# USB2517.net
KiCad netlist of a schematic drawn in Altium Designer
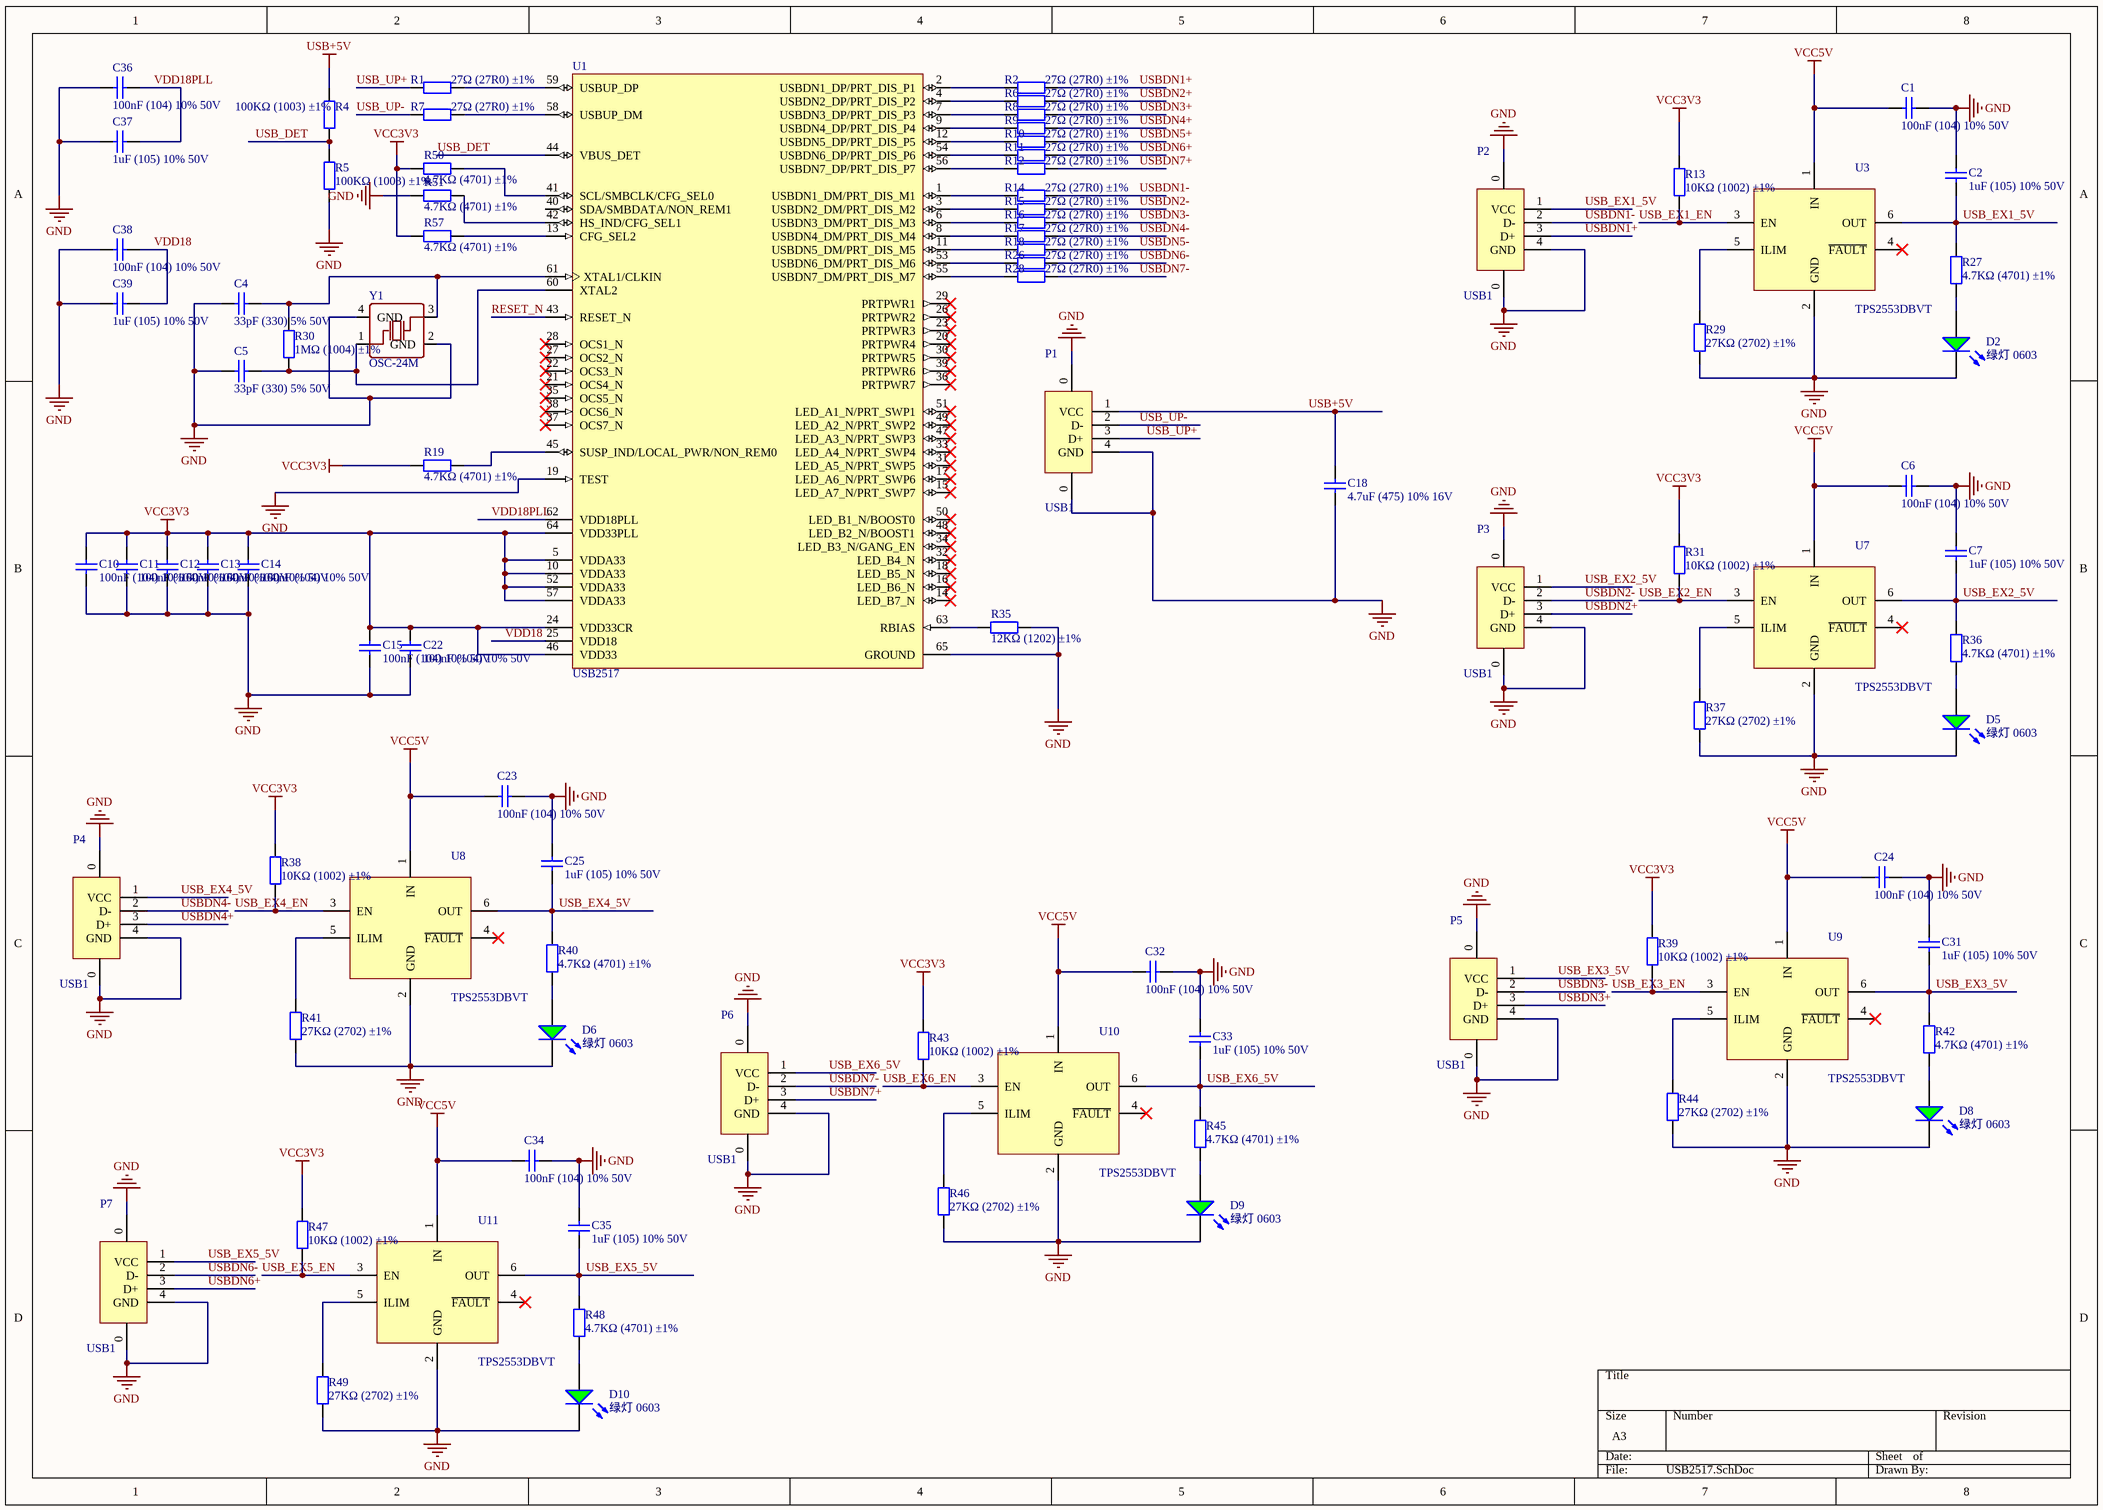
[diagram p0: USB2517.SchDoc]

(export (version "E")
  (design (tool "Eeschema 10.0.6"))
  (components
    (comp (ref "C1")
      (value "100nF (104) 10% 50V")
      (footprint "0603_C")
      (description "贴片电容")
      (libsource (lib "AD封装2018.9.19Miscellaneous Devices LC") (part "0603 100nF (104) 10% 50V"))
    )
    (comp (ref "C2")
      (value "1uF (105) 10% 50V")
      (footprint "0603_C")
      (description "贴片电容")
      (libsource (lib "AD封装2018.9.19Miscellaneous Devices LC") (part "0603 1uF (105) 10% 50V"))
    )
    (comp (ref "C4")
      (value "33pF (330) 5% 50V")
      (footprint "0603_C")
      (description "贴片电容")
      (libsource (lib "AD封装2018.9.19Miscellaneous Devices LC") (part "0603 33pF (330) 5% 50V"))
    )
    (comp (ref "C5")
      (value "33pF (330) 5% 50V")
      (footprint "0603_C")
      (description "贴片电容")
      (libsource (lib "AD封装2018.9.19Miscellaneous Devices LC") (part "0603 33pF (330) 5% 50V"))
    )
    (comp (ref "C6")
      (value "100nF (104) 10% 50V")
      (footprint "0603_C")
      (description "贴片电容")
      (libsource (lib "AD封装2018.9.19Miscellaneous Devices LC") (part "0603 100nF (104) 10% 50V"))
    )
    (comp (ref "C7")
      (value "1uF (105) 10% 50V")
      (footprint "0603_C")
      (description "贴片电容")
      (libsource (lib "AD封装2018.9.19Miscellaneous Devices LC") (part "0603 1uF (105) 10% 50V"))
    )
    (comp (ref "C10")
      (value "100nF (104) 10% 50V")
      (footprint "0603_C")
      (description "贴片电容")
      (libsource (lib "AD封装2018.9.19Miscellaneous Devices LC") (part "0603 100nF (104) 10% 50V"))
    )
    (comp (ref "C11")
      (value "100nF (104) 10% 50V")
      (footprint "0603_C")
      (description "贴片电容")
      (libsource (lib "AD封装2018.9.19Miscellaneous Devices LC") (part "0603 100nF (104) 10% 50V"))
    )
    (comp (ref "C12")
      (value "100nF (104) 10% 50V")
      (footprint "0603_C")
      (description "贴片电容")
      (libsource (lib "AD封装2018.9.19Miscellaneous Devices LC") (part "0603 100nF (104) 10% 50V"))
    )
    (comp (ref "C13")
      (value "100nF (104) 10% 50V")
      (footprint "0603_C")
      (description "贴片电容")
      (libsource (lib "AD封装2018.9.19Miscellaneous Devices LC") (part "0603 100nF (104) 10% 50V"))
    )
    (comp (ref "C14")
      (value "100nF (104) 10% 50V")
      (footprint "0603_C")
      (description "贴片电容")
      (libsource (lib "AD封装2018.9.19Miscellaneous Devices LC") (part "0603 100nF (104) 10% 50V"))
    )
    (comp (ref "C15")
      (value "100nF (104) 10% 50V")
      (footprint "0603_C")
      (description "贴片电容")
      (libsource (lib "AD封装2018.9.19Miscellaneous Devices LC") (part "0603 100nF (104) 10% 50V"))
    )
    (comp (ref "C18")
      (value "4.7uF (475) 10% 16V")
      (footprint "0603_C")
      (description "贴片电容")
      (libsource (lib "AD封装2018.9.19Miscellaneous Devices LC") (part "0603 4.7uF (475) 10% 16V"))
    )
    (comp (ref "C22")
      (value "100nF (104) 10% 50V")
      (footprint "0603_C")
      (description "贴片电容")
      (libsource (lib "AD封装2018.9.19Miscellaneous Devices LC") (part "0603 100nF (104) 10% 50V"))
    )
    (comp (ref "C23")
      (value "100nF (104) 10% 50V")
      (footprint "0603_C")
      (description "贴片电容")
      (libsource (lib "AD封装2018.9.19Miscellaneous Devices LC") (part "0603 100nF (104) 10% 50V"))
    )
    (comp (ref "C24")
      (value "100nF (104) 10% 50V")
      (footprint "0603_C")
      (description "贴片电容")
      (libsource (lib "AD封装2018.9.19Miscellaneous Devices LC") (part "0603 100nF (104) 10% 50V"))
    )
    (comp (ref "C25")
      (value "1uF (105) 10% 50V")
      (footprint "0603_C")
      (description "贴片电容")
      (libsource (lib "AD封装2018.9.19Miscellaneous Devices LC") (part "0603 1uF (105) 10% 50V"))
    )
    (comp (ref "C31")
      (value "1uF (105) 10% 50V")
      (footprint "0603_C")
      (description "贴片电容")
      (libsource (lib "AD封装2018.9.19Miscellaneous Devices LC") (part "0603 1uF (105) 10% 50V"))
    )
    (comp (ref "C32")
      (value "100nF (104) 10% 50V")
      (footprint "0603_C")
      (description "贴片电容")
      (libsource (lib "AD封装2018.9.19Miscellaneous Devices LC") (part "0603 100nF (104) 10% 50V"))
    )
    (comp (ref "C33")
      (value "1uF (105) 10% 50V")
      (footprint "0603_C")
      (description "贴片电容")
      (libsource (lib "AD封装2018.9.19Miscellaneous Devices LC") (part "0603 1uF (105) 10% 50V"))
    )
    (comp (ref "C34")
      (value "100nF (104) 10% 50V")
      (footprint "0603_C")
      (description "贴片电容")
      (libsource (lib "AD封装2018.9.19Miscellaneous Devices LC") (part "0603 100nF (104) 10% 50V"))
    )
    (comp (ref "C35")
      (value "1uF (105) 10% 50V")
      (footprint "0603_C")
      (description "贴片电容")
      (libsource (lib "AD封装2018.9.19Miscellaneous Devices LC") (part "0603 1uF (105) 10% 50V"))
    )
    (comp (ref "C36")
      (value "100nF (104) 10% 50V")
      (footprint "0603_C")
      (description "贴片电容")
      (libsource (lib "AD封装2018.9.19Miscellaneous Devices LC") (part "0603 100nF (104) 10% 50V"))
    )
    (comp (ref "C37")
      (value "1uF (105) 10% 50V")
      (footprint "0603_C")
      (description "贴片电容")
      (libsource (lib "AD封装2018.9.19Miscellaneous Devices LC") (part "0603 1uF (105) 10% 50V"))
    )
    (comp (ref "C38")
      (value "100nF (104) 10% 50V")
      (footprint "0603_C")
      (description "贴片电容")
      (libsource (lib "AD封装2018.9.19Miscellaneous Devices LC") (part "0603 100nF (104) 10% 50V"))
    )
    (comp (ref "C39")
      (value "1uF (105) 10% 50V")
      (footprint "0603_C")
      (description "贴片电容")
      (libsource (lib "AD封装2018.9.19Miscellaneous Devices LC") (part "0603 1uF (105) 10% 50V"))
    )
    (comp (ref "D2")
      (value "绿灯 0603")
      (footprint "0603_LED_S1")
      (description "发光二极管")
      (libsource (lib "AD封装2018.9.19Miscellaneous Devices LC") (part "0603 绿灯"))
    )
    (comp (ref "D5")
      (value "绿灯 0603")
      (footprint "0603_LED_S1")
      (description "发光二极管")
      (libsource (lib "AD封装2018.9.19Miscellaneous Devices LC") (part "0603 绿灯"))
    )
    (comp (ref "D6")
      (value "绿灯 0603")
      (footprint "0603_LED_S1")
      (description "发光二极管")
      (libsource (lib "AD封装2018.9.19Miscellaneous Devices LC") (part "0603 绿灯"))
    )
    (comp (ref "D8")
      (value "绿灯 0603")
      (footprint "0603_LED_S1")
      (description "发光二极管")
      (libsource (lib "AD封装2018.9.19Miscellaneous Devices LC") (part "0603 绿灯"))
    )
    (comp (ref "D9")
      (value "绿灯 0603")
      (footprint "0603_LED_S1")
      (description "发光二极管")
      (libsource (lib "AD封装2018.9.19Miscellaneous Devices LC") (part "0603 绿灯"))
    )
    (comp (ref "D10")
      (value "绿灯 0603")
      (footprint "0603_LED_S1")
      (description "发光二极管")
      (libsource (lib "AD封装2018.9.19Miscellaneous Devices LC") (part "0603 绿灯"))
    )
    (comp (ref "P1") (value "USB1") (footprint "USB-B-TH_USB-B01") (libsource (lib "我的集成库") (part "USB1")))
    (comp (ref "P2")
      (value "USB1")
      (footprint "USB-A-TH_AF90-OFFSET - duplicate")
      (libsource (lib "我的集成库") (part "USB1"))
    )
    (comp (ref "P3")
      (value "USB1")
      (footprint "USB-A-TH_AF90-OFFSET - duplicate")
      (libsource (lib "我的集成库") (part "USB1"))
    )
    (comp (ref "P4")
      (value "USB1")
      (footprint "USB-A-TH_AF90-OFFSET - duplicate")
      (libsource (lib "我的集成库") (part "USB1"))
    )
    (comp (ref "P5")
      (value "USB1")
      (footprint "USB-A-TH_AF90-OFFSET - duplicate")
      (libsource (lib "我的集成库") (part "USB1"))
    )
    (comp (ref "P6")
      (value "USB1")
      (footprint "USB-A-TH_AF90-OFFSET - duplicate")
      (libsource (lib "我的集成库") (part "USB1"))
    )
    (comp (ref "P7")
      (value "USB1")
      (footprint "USB-A-TH_AF90-OFFSET - duplicate")
      (libsource (lib "我的集成库") (part "USB1"))
    )
    (comp (ref "R1")
      (value "27Ω (27R0) ±1%")
      (footprint "0603_R")
      (description "贴片电阻")
      (libsource (lib "AD封装2018.9.19Miscellaneous Devices LC") (part "0603 27Ω (27R0) 1%"))
    )
    (comp (ref "R2")
      (value "27Ω (27R0) ±1%")
      (footprint "0603_R")
      (description "贴片电阻")
      (libsource (lib "AD封装2018.9.19Miscellaneous Devices LC") (part "0603 27Ω (27R0) 1%"))
    )
    (comp (ref "R4")
      (value "100KΩ (1003) ±1%")
      (footprint "0603_R")
      (description "贴片电阻")
      (libsource (lib "AD封装2018.9.19Miscellaneous Devices LC") (part "0603 100KΩ (1003) 1%"))
    )
    (comp (ref "R5")
      (value "100KΩ (1003) ±1%")
      (footprint "0603_R")
      (description "贴片电阻")
      (libsource (lib "AD封装2018.9.19Miscellaneous Devices LC") (part "0603 100KΩ (1003) 1%"))
    )
    (comp (ref "R6")
      (value "27Ω (27R0) ±1%")
      (footprint "0603_R")
      (description "贴片电阻")
      (libsource (lib "AD封装2018.9.19Miscellaneous Devices LC") (part "0603 27Ω (27R0) 1%"))
    )
    (comp (ref "R7")
      (value "27Ω (27R0) ±1%")
      (footprint "0603_R")
      (description "贴片电阻")
      (libsource (lib "AD封装2018.9.19Miscellaneous Devices LC") (part "0603 27Ω (27R0) 1%"))
    )
    (comp (ref "R8")
      (value "27Ω (27R0) ±1%")
      (footprint "0603_R")
      (description "贴片电阻")
      (libsource (lib "AD封装2018.9.19Miscellaneous Devices LC") (part "0603 27Ω (27R0) 1%"))
    )
    (comp (ref "R9")
      (value "27Ω (27R0) ±1%")
      (footprint "0603_R")
      (description "贴片电阻")
      (libsource (lib "AD封装2018.9.19Miscellaneous Devices LC") (part "0603 27Ω (27R0) 1%"))
    )
    (comp (ref "R10")
      (value "27Ω (27R0) ±1%")
      (footprint "0603_R")
      (description "贴片电阻")
      (libsource (lib "AD封装2018.9.19Miscellaneous Devices LC") (part "0603 27Ω (27R0) 1%"))
    )
    (comp (ref "R11")
      (value "27Ω (27R0) ±1%")
      (footprint "0603_R")
      (description "贴片电阻")
      (libsource (lib "AD封装2018.9.19Miscellaneous Devices LC") (part "0603 27Ω (27R0) 1%"))
    )
    (comp (ref "R12")
      (value "27Ω (27R0) ±1%")
      (footprint "0603_R")
      (description "贴片电阻")
      (libsource (lib "AD封装2018.9.19Miscellaneous Devices LC") (part "0603 27Ω (27R0) 1%"))
    )
    (comp (ref "R13")
      (value "10KΩ (1002) ±1%")
      (footprint "0603_R")
      (description "贴片电阻")
      (libsource (lib "AD封装2018.9.19Miscellaneous Devices LC") (part "0603 10KΩ (1002) 1%"))
    )
    (comp (ref "R14")
      (value "27Ω (27R0) ±1%")
      (footprint "0603_R")
      (description "贴片电阻")
      (libsource (lib "AD封装2018.9.19Miscellaneous Devices LC") (part "0603 27Ω (27R0) 1%"))
    )
    (comp (ref "R15")
      (value "27Ω (27R0) ±1%")
      (footprint "0603_R")
      (description "贴片电阻")
      (libsource (lib "AD封装2018.9.19Miscellaneous Devices LC") (part "0603 27Ω (27R0) 1%"))
    )
    (comp (ref "R16")
      (value "27Ω (27R0) ±1%")
      (footprint "0603_R")
      (description "贴片电阻")
      (libsource (lib "AD封装2018.9.19Miscellaneous Devices LC") (part "0603 27Ω (27R0) 1%"))
    )
    (comp (ref "R17")
      (value "27Ω (27R0) ±1%")
      (footprint "0603_R")
      (description "贴片电阻")
      (libsource (lib "AD封装2018.9.19Miscellaneous Devices LC") (part "0603 27Ω (27R0) 1%"))
    )
    (comp (ref "R18")
      (value "27Ω (27R0) ±1%")
      (footprint "0603_R")
      (description "贴片电阻")
      (libsource (lib "AD封装2018.9.19Miscellaneous Devices LC") (part "0603 27Ω (27R0) 1%"))
    )
    (comp (ref "R19")
      (value "4.7KΩ (4701) ±1%")
      (footprint "0603_R")
      (description "贴片电阻")
      (libsource (lib "") (part "0603 4.7KΩ (4701) 1%_2"))
    )
    (comp (ref "R26")
      (value "27Ω (27R0) ±1%")
      (footprint "0603_R")
      (description "贴片电阻")
      (libsource (lib "AD封装2018.9.19Miscellaneous Devices LC") (part "0603 27Ω (27R0) 1%"))
    )
    (comp (ref "R27")
      (value "4.7KΩ (4701) ±1%")
      (footprint "0603_R")
      (description "贴片电阻")
      (libsource (lib "AD封装2018.9.19Miscellaneous Devices LC") (part "0603 4.7KΩ (4701) 1%"))
    )
    (comp (ref "R28")
      (value "27Ω (27R0) ±1%")
      (footprint "0603_R")
      (description "贴片电阻")
      (libsource (lib "AD封装2018.9.19Miscellaneous Devices LC") (part "0603 27Ω (27R0) 1%"))
    )
    (comp (ref "R29")
      (value "27KΩ (2702) ±1%")
      (footprint "0603_R")
      (description "贴片电阻")
      (libsource (lib "AD封装2018.9.19Miscellaneous Devices LC") (part "0603 27KΩ (2702) 1%"))
    )
    (comp (ref "R30")
      (value "1MΩ (1004) ±1%")
      (footprint "0603_R")
      (description "贴片电阻")
      (libsource (lib "AD封装2018.9.19Miscellaneous Devices LC") (part "0603 1MΩ (1004) 1%"))
    )
    (comp (ref "R31")
      (value "10KΩ (1002) ±1%")
      (footprint "0603_R")
      (description "贴片电阻")
      (libsource (lib "AD封装2018.9.19Miscellaneous Devices LC") (part "0603 10KΩ (1002) 1%"))
    )
    (comp (ref "R35")
      (value "12KΩ (1202) ±1%")
      (footprint "0603_R")
      (description "贴片电阻")
      (libsource (lib "AD封装2018.9.19Miscellaneous Devices LC") (part "0603 12KΩ (1202) 1%"))
    )
    (comp (ref "R36")
      (value "4.7KΩ (4701) ±1%")
      (footprint "0603_R")
      (description "贴片电阻")
      (libsource (lib "AD封装2018.9.19Miscellaneous Devices LC") (part "0603 4.7KΩ (4701) 1%"))
    )
    (comp (ref "R37")
      (value "27KΩ (2702) ±1%")
      (footprint "0603_R")
      (description "贴片电阻")
      (libsource (lib "AD封装2018.9.19Miscellaneous Devices LC") (part "0603 27KΩ (2702) 1%"))
    )
    (comp (ref "R38")
      (value "10KΩ (1002) ±1%")
      (footprint "0603_R")
      (description "贴片电阻")
      (libsource (lib "AD封装2018.9.19Miscellaneous Devices LC") (part "0603 10KΩ (1002) 1%"))
    )
    (comp (ref "R39")
      (value "10KΩ (1002) ±1%")
      (footprint "0603_R")
      (description "贴片电阻")
      (libsource (lib "AD封装2018.9.19Miscellaneous Devices LC") (part "0603 10KΩ (1002) 1%"))
    )
    (comp (ref "R40")
      (value "4.7KΩ (4701) ±1%")
      (footprint "0603_R")
      (description "贴片电阻")
      (libsource (lib "AD封装2018.9.19Miscellaneous Devices LC") (part "0603 4.7KΩ (4701) 1%"))
    )
    (comp (ref "R41")
      (value "27KΩ (2702) ±1%")
      (footprint "0603_R")
      (description "贴片电阻")
      (libsource (lib "AD封装2018.9.19Miscellaneous Devices LC") (part "0603 27KΩ (2702) 1%"))
    )
    (comp (ref "R42")
      (value "4.7KΩ (4701) ±1%")
      (footprint "0603_R")
      (description "贴片电阻")
      (libsource (lib "AD封装2018.9.19Miscellaneous Devices LC") (part "0603 4.7KΩ (4701) 1%"))
    )
    (comp (ref "R43")
      (value "10KΩ (1002) ±1%")
      (footprint "0603_R")
      (description "贴片电阻")
      (libsource (lib "AD封装2018.9.19Miscellaneous Devices LC") (part "0603 10KΩ (1002) 1%"))
    )
    (comp (ref "R44")
      (value "27KΩ (2702) ±1%")
      (footprint "0603_R")
      (description "贴片电阻")
      (libsource (lib "AD封装2018.9.19Miscellaneous Devices LC") (part "0603 27KΩ (2702) 1%"))
    )
    (comp (ref "R45")
      (value "4.7KΩ (4701) ±1%")
      (footprint "0603_R")
      (description "贴片电阻")
      (libsource (lib "AD封装2018.9.19Miscellaneous Devices LC") (part "0603 4.7KΩ (4701) 1%"))
    )
    (comp (ref "R46")
      (value "27KΩ (2702) ±1%")
      (footprint "0603_R")
      (description "贴片电阻")
      (libsource (lib "AD封装2018.9.19Miscellaneous Devices LC") (part "0603 27KΩ (2702) 1%"))
    )
    (comp (ref "R47")
      (value "10KΩ (1002) ±1%")
      (footprint "0603_R")
      (description "贴片电阻")
      (libsource (lib "AD封装2018.9.19Miscellaneous Devices LC") (part "0603 10KΩ (1002) 1%"))
    )
    (comp (ref "R48")
      (value "4.7KΩ (4701) ±1%")
      (footprint "0603_R")
      (description "贴片电阻")
      (libsource (lib "AD封装2018.9.19Miscellaneous Devices LC") (part "0603 4.7KΩ (4701) 1%"))
    )
    (comp (ref "R49")
      (value "27KΩ (2702) ±1%")
      (footprint "0603_R")
      (description "贴片电阻")
      (libsource (lib "AD封装2018.9.19Miscellaneous Devices LC") (part "0603 27KΩ (2702) 1%"))
    )
    (comp (ref "R50")
      (value "4.7KΩ (4701) ±1%")
      (footprint "0603_R")
      (description "贴片电阻")
      (libsource (lib "") (part "0603 4.7KΩ (4701) 1%_1"))
    )
    (comp (ref "R51")
      (value "4.7KΩ (4701) ±1%")
      (footprint "0603_R")
      (description "贴片电阻")
      (libsource (lib "") (part "0603 4.7KΩ (4701) 1%_1"))
    )
    (comp (ref "R57")
      (value "4.7KΩ (4701) ±1%")
      (footprint "0603_R")
      (description "贴片电阻")
      (libsource (lib "") (part "0603 4.7KΩ (4701) 1%_1"))
    )
    (comp (ref "U1") (value "USB2517") (footprint "QFN-64") (libsource (lib "我的集成库") (part "USB2517-JZX")))
    (comp (ref "U3")
      (value "TPS2553DBVT")
      (footprint "SOT-23-6")
      (description "SOT-23-6")
      (libsource (lib "我的集成库") (part "TPS2553DBVT"))
    )
    (comp (ref "U7")
      (value "TPS2553DBVT")
      (footprint "SOT-23-6")
      (description "SOT-23-6")
      (libsource (lib "我的集成库") (part "TPS2553DBVT"))
    )
    (comp (ref "U8")
      (value "TPS2553DBVT")
      (footprint "SOT-23-6")
      (description "SOT-23-6")
      (libsource (lib "我的集成库") (part "TPS2553DBVT"))
    )
    (comp (ref "U9")
      (value "TPS2553DBVT")
      (footprint "SOT-23-6")
      (description "SOT-23-6")
      (libsource (lib "我的集成库") (part "TPS2553DBVT"))
    )
    (comp (ref "U10")
      (value "TPS2553DBVT")
      (footprint "SOT-23-6")
      (description "SOT-23-6")
      (libsource (lib "我的集成库") (part "TPS2553DBVT"))
    )
    (comp (ref "U11")
      (value "TPS2553DBVT")
      (footprint "SOT-23-6")
      (description "SOT-23-6")
      (libsource (lib "我的集成库") (part "TPS2553DBVT"))
    )
    (comp (ref "Y1")
      (value "OSC-24M")
      (footprint "SMD-3225_4P")
      (description "SMD-3225_4P")
      (libsource (lib "我的集成库") (part "OSC-24M"))
    )
  )
  (nets
    (net (code "1") (name "/RESET_N") (class "Default")
      (node (ref "U1") (pin "43") (pinfunction "RESET_N_43") (pintype "input"))
    )
    (net (code "2") (name "/USBDN1+") (class "Default")
      (node (ref "P2") (pin "3") (pinfunction "D+_3") (pintype "passive"))
      (node (ref "R2") (pin "2") (pinfunction "2_2") (pintype "passive"))
    )
    (net (code "3") (name "/USBDN1-") (class "Default")
      (node (ref "P2") (pin "2") (pinfunction "D-_2") (pintype "passive"))
      (node (ref "R14") (pin "2") (pinfunction "2_2") (pintype "passive"))
    )
    (net (code "4") (name "/USBDN2+") (class "Default")
      (node (ref "P3") (pin "3") (pinfunction "D+_3") (pintype "passive"))
      (node (ref "R6") (pin "2") (pinfunction "2_2") (pintype "passive"))
    )
    (net (code "5") (name "/USBDN2-") (class "Default")
      (node (ref "P3") (pin "2") (pinfunction "D-_2") (pintype "passive"))
      (node (ref "R15") (pin "2") (pinfunction "2_2") (pintype "passive"))
    )
    (net (code "6") (name "/USBDN3+") (class "Default")
      (node (ref "P5") (pin "3") (pinfunction "D+_3") (pintype "passive"))
      (node (ref "R8") (pin "2") (pinfunction "2_2") (pintype "passive"))
    )
    (net (code "7") (name "/USBDN3-") (class "Default")
      (node (ref "P5") (pin "2") (pinfunction "D-_2") (pintype "passive"))
      (node (ref "R16") (pin "2") (pinfunction "2_2") (pintype "passive"))
    )
    (net (code "8") (name "/USBDN4+") (class "Default")
      (node (ref "P4") (pin "3") (pinfunction "D+_3") (pintype "passive"))
      (node (ref "R9") (pin "2") (pinfunction "2_2") (pintype "passive"))
    )
    (net (code "9") (name "/USBDN4-") (class "Default")
      (node (ref "P4") (pin "2") (pinfunction "D-_2") (pintype "passive"))
      (node (ref "R17") (pin "2") (pinfunction "2_2") (pintype "passive"))
    )
    (net (code "10") (name "/USBDN5+") (class "Default")
      (node (ref "R10") (pin "2") (pinfunction "2_2") (pintype "passive"))
    )
    (net (code "11") (name "/USBDN5-") (class "Default")
      (node (ref "R18") (pin "2") (pinfunction "2_2") (pintype "passive"))
    )
    (net (code "12") (name "/USBDN6+") (class "Default")
      (node (ref "P7") (pin "3") (pinfunction "D+_3") (pintype "passive"))
      (node (ref "R11") (pin "2") (pinfunction "2_2") (pintype "passive"))
    )
    (net (code "13") (name "/USBDN6-") (class "Default")
      (node (ref "P7") (pin "2") (pinfunction "D-_2") (pintype "passive"))
      (node (ref "R26") (pin "2") (pinfunction "2_2") (pintype "passive"))
    )
    (net (code "14") (name "/USBDN7+") (class "Default")
      (node (ref "P6") (pin "3") (pinfunction "D+_3") (pintype "passive"))
      (node (ref "R12") (pin "2") (pinfunction "2_2") (pintype "passive"))
    )
    (net (code "15") (name "/USBDN7-") (class "Default")
      (node (ref "P6") (pin "2") (pinfunction "D-_2") (pintype "passive"))
      (node (ref "R28") (pin "2") (pinfunction "2_2") (pintype "passive"))
    )
    (net (code "16") (name "/USB_DET") (class "Default")
      (node (ref "R4") (pin "1") (pinfunction "1_1") (pintype "passive"))
      (node (ref "R5") (pin "2") (pinfunction "2_2") (pintype "passive"))
      (node (ref "U1") (pin "44") (pinfunction "VBUS_DET_44") (pintype "bidirectional"))
    )
    (net (code "17") (name "/USB_EX1_5V") (class "Default")
      (node (ref "C2") (pin "1") (pinfunction "1_1") (pintype "passive"))
      (node (ref "P2") (pin "1") (pinfunction "VCC_1") (pintype "passive"))
      (node (ref "R27") (pin "2") (pinfunction "2_2") (pintype "passive"))
      (node (ref "U3") (pin "6") (pinfunction "OUT_6") (pintype "passive"))
    )
    (net (code "18") (name "/USB_EX1_EN") (class "Default")
      (node (ref "R13") (pin "1") (pinfunction "1_1") (pintype "passive"))
      (node (ref "U3") (pin "3") (pinfunction "EN_3") (pintype "passive"))
    )
    (net (code "19") (name "/USB_EX2_5V") (class "Default")
      (node (ref "C7") (pin "1") (pinfunction "1_1") (pintype "passive"))
      (node (ref "P3") (pin "1") (pinfunction "VCC_1") (pintype "passive"))
      (node (ref "R36") (pin "2") (pinfunction "2_2") (pintype "passive"))
      (node (ref "U7") (pin "6") (pinfunction "OUT_6") (pintype "passive"))
    )
    (net (code "20") (name "/USB_EX2_EN") (class "Default")
      (node (ref "R31") (pin "1") (pinfunction "1_1") (pintype "passive"))
      (node (ref "U7") (pin "3") (pinfunction "EN_3") (pintype "passive"))
    )
    (net (code "21") (name "/USB_EX3_5V") (class "Default")
      (node (ref "C31") (pin "1") (pinfunction "1_1") (pintype "passive"))
      (node (ref "P5") (pin "1") (pinfunction "VCC_1") (pintype "passive"))
      (node (ref "R42") (pin "2") (pinfunction "2_2") (pintype "passive"))
      (node (ref "U9") (pin "6") (pinfunction "OUT_6") (pintype "passive"))
    )
    (net (code "22") (name "/USB_EX3_EN") (class "Default")
      (node (ref "R39") (pin "1") (pinfunction "1_1") (pintype "passive"))
      (node (ref "U9") (pin "3") (pinfunction "EN_3") (pintype "passive"))
    )
    (net (code "23") (name "/USB_EX4_5V") (class "Default")
      (node (ref "C25") (pin "1") (pinfunction "1_1") (pintype "passive"))
      (node (ref "P4") (pin "1") (pinfunction "VCC_1") (pintype "passive"))
      (node (ref "R40") (pin "2") (pinfunction "2_2") (pintype "passive"))
      (node (ref "U8") (pin "6") (pinfunction "OUT_6") (pintype "passive"))
    )
    (net (code "24") (name "/USB_EX4_EN") (class "Default")
      (node (ref "R38") (pin "1") (pinfunction "1_1") (pintype "passive"))
      (node (ref "U8") (pin "3") (pinfunction "EN_3") (pintype "passive"))
    )
    (net (code "25") (name "/USB_EX5_5V") (class "Default")
      (node (ref "C35") (pin "1") (pinfunction "1_1") (pintype "passive"))
      (node (ref "P7") (pin "1") (pinfunction "VCC_1") (pintype "passive"))
      (node (ref "R48") (pin "2") (pinfunction "2_2") (pintype "passive"))
      (node (ref "U11") (pin "6") (pinfunction "OUT_6") (pintype "passive"))
    )
    (net (code "26") (name "/USB_EX5_EN") (class "Default")
      (node (ref "R47") (pin "1") (pinfunction "1_1") (pintype "passive"))
      (node (ref "U11") (pin "3") (pinfunction "EN_3") (pintype "passive"))
    )
    (net (code "27") (name "/USB_EX6_5V") (class "Default")
      (node (ref "C33") (pin "1") (pinfunction "1_1") (pintype "passive"))
      (node (ref "P6") (pin "1") (pinfunction "VCC_1") (pintype "passive"))
      (node (ref "R45") (pin "2") (pinfunction "2_2") (pintype "passive"))
      (node (ref "U10") (pin "6") (pinfunction "OUT_6") (pintype "passive"))
    )
    (net (code "28") (name "/USB_EX6_EN") (class "Default")
      (node (ref "R43") (pin "1") (pinfunction "1_1") (pintype "passive"))
      (node (ref "U10") (pin "3") (pinfunction "EN_3") (pintype "passive"))
    )
    (net (code "29") (name "/USB_UP+") (class "Default")
      (node (ref "P1") (pin "3") (pinfunction "D+_3") (pintype "passive"))
      (node (ref "R1") (pin "1") (pinfunction "1_1") (pintype "passive"))
    )
    (net (code "30") (name "/USB_UP-") (class "Default")
      (node (ref "P1") (pin "2") (pinfunction "D-_2") (pintype "passive"))
      (node (ref "R7") (pin "1") (pinfunction "1_1") (pintype "passive"))
    )
    (net (code "31") (name "/VDD18") (class "Default")
      (node (ref "C38") (pin "2") (pinfunction "2_2") (pintype "passive"))
      (node (ref "C39") (pin "2") (pinfunction "2_2") (pintype "passive"))
      (node (ref "U1") (pin "25") (pinfunction "VDD18_25") (pintype "power_in"))
    )
    (net (code "32") (name "/VDD18PLL") (class "Default")
      (node (ref "C36") (pin "2") (pinfunction "2_2") (pintype "passive"))
      (node (ref "C37") (pin "2") (pinfunction "2_2") (pintype "passive"))
      (node (ref "U1") (pin "62") (pinfunction "VDD18PLL_62") (pintype "power_in"))
    )
    (net (code "33") (name "GND") (class "Default")
      (node (ref "C1") (pin "2") (pinfunction "2_2") (pintype "passive"))
      (node (ref "C10") (pin "2") (pinfunction "2_2") (pintype "passive"))
      (node (ref "C11") (pin "1") (pinfunction "1_1") (pintype "passive"))
      (node (ref "C12") (pin "1") (pinfunction "1_1") (pintype "passive"))
      (node (ref "C13") (pin "1") (pinfunction "1_1") (pintype "passive"))
      (node (ref "C14") (pin "1") (pinfunction "1_1") (pintype "passive"))
      (node (ref "C15") (pin "1") (pinfunction "1_1") (pintype "passive"))
      (node (ref "C18") (pin "1") (pinfunction "1_1") (pintype "passive"))
      (node (ref "C2") (pin "2") (pinfunction "2_2") (pintype "passive"))
      (node (ref "C22") (pin "1") (pinfunction "1_1") (pintype "passive"))
      (node (ref "C23") (pin "2") (pinfunction "2_2") (pintype "passive"))
      (node (ref "C24") (pin "2") (pinfunction "2_2") (pintype "passive"))
      (node (ref "C25") (pin "2") (pinfunction "2_2") (pintype "passive"))
      (node (ref "C31") (pin "2") (pinfunction "2_2") (pintype "passive"))
      (node (ref "C32") (pin "2") (pinfunction "2_2") (pintype "passive"))
      (node (ref "C33") (pin "2") (pinfunction "2_2") (pintype "passive"))
      (node (ref "C34") (pin "2") (pinfunction "2_2") (pintype "passive"))
      (node (ref "C35") (pin "2") (pinfunction "2_2") (pintype "passive"))
      (node (ref "C36") (pin "1") (pinfunction "1_1") (pintype "passive"))
      (node (ref "C37") (pin "1") (pinfunction "1_1") (pintype "passive"))
      (node (ref "C38") (pin "1") (pinfunction "1_1") (pintype "passive"))
      (node (ref "C39") (pin "1") (pinfunction "1_1") (pintype "passive"))
      (node (ref "C4") (pin "1") (pinfunction "1_1") (pintype "passive"))
      (node (ref "C5") (pin "1") (pinfunction "1_1") (pintype "passive"))
      (node (ref "C6") (pin "2") (pinfunction "2_2") (pintype "passive"))
      (node (ref "C7") (pin "2") (pinfunction "2_2") (pintype "passive"))
      (node (ref "D10") (pin "K") (pinfunction "K_K") (pintype "passive"))
      (node (ref "D2") (pin "K") (pinfunction "K_K") (pintype "passive"))
      (node (ref "D5") (pin "K") (pinfunction "K_K") (pintype "passive"))
      (node (ref "D6") (pin "K") (pinfunction "K_K") (pintype "passive"))
      (node (ref "D8") (pin "K") (pinfunction "K_K") (pintype "passive"))
      (node (ref "D9") (pin "K") (pinfunction "K_K") (pintype "passive"))
      (node (ref "P1") (pin "0") (pinfunction "0_0") (pintype "passive"))
      (node (ref "P1") (pin "4") (pinfunction "GND_4") (pintype "passive"))
      (node (ref "P2") (pin "0") (pinfunction "0_0") (pintype "passive"))
      (node (ref "P2") (pin "4") (pinfunction "GND_4") (pintype "passive"))
      (node (ref "P3") (pin "0") (pinfunction "0_0") (pintype "passive"))
      (node (ref "P3") (pin "4") (pinfunction "GND_4") (pintype "passive"))
      (node (ref "P4") (pin "0") (pinfunction "0_0") (pintype "passive"))
      (node (ref "P4") (pin "4") (pinfunction "GND_4") (pintype "passive"))
      (node (ref "P5") (pin "0") (pinfunction "0_0") (pintype "passive"))
      (node (ref "P5") (pin "4") (pinfunction "GND_4") (pintype "passive"))
      (node (ref "P6") (pin "0") (pinfunction "0_0") (pintype "passive"))
      (node (ref "P6") (pin "4") (pinfunction "GND_4") (pintype "passive"))
      (node (ref "P7") (pin "0") (pinfunction "0_0") (pintype "passive"))
      (node (ref "P7") (pin "4") (pinfunction "GND_4") (pintype "passive"))
      (node (ref "R29") (pin "1") (pinfunction "1_1") (pintype "passive"))
      (node (ref "R35") (pin "2") (pinfunction "2_2") (pintype "passive"))
      (node (ref "R37") (pin "1") (pinfunction "1_1") (pintype "passive"))
      (node (ref "R41") (pin "1") (pinfunction "1_1") (pintype "passive"))
      (node (ref "R44") (pin "1") (pinfunction "1_1") (pintype "passive"))
      (node (ref "R46") (pin "1") (pinfunction "1_1") (pintype "passive"))
      (node (ref "R49") (pin "1") (pinfunction "1_1") (pintype "passive"))
      (node (ref "R5") (pin "1") (pinfunction "1_1") (pintype "passive"))
      (node (ref "R51") (pin "1") (pinfunction "1_1") (pintype "passive"))
      (node (ref "U1") (pin "19") (pinfunction "TEST_19") (pintype "input"))
      (node (ref "U1") (pin "65") (pinfunction "GROUND_65") (pintype "power_in"))
      (node (ref "U10") (pin "2") (pinfunction "GND_2") (pintype "passive"))
      (node (ref "U11") (pin "2") (pinfunction "GND_2") (pintype "passive"))
      (node (ref "U3") (pin "2") (pinfunction "GND_2") (pintype "passive"))
      (node (ref "U7") (pin "2") (pinfunction "GND_2") (pintype "passive"))
      (node (ref "U8") (pin "2") (pinfunction "GND_2") (pintype "passive"))
      (node (ref "U9") (pin "2") (pinfunction "GND_2") (pintype "passive"))
      (node (ref "Y1") (pin "2") (pinfunction "GND_2") (pintype "passive"))
      (node (ref "Y1") (pin "4") (pinfunction "GND_4") (pintype "passive"))
    )
    (net (code "34") (name "Net-(D2-PadA)") (class "Default")
      (node (ref "D2") (pin "A") (pinfunction "A_A") (pintype "passive"))
      (node (ref "R27") (pin "1") (pinfunction "1_1") (pintype "passive"))
    )
    (net (code "35") (name "Net-(D5-PadA)") (class "Default")
      (node (ref "D5") (pin "A") (pinfunction "A_A") (pintype "passive"))
      (node (ref "R36") (pin "1") (pinfunction "1_1") (pintype "passive"))
    )
    (net (code "36") (name "Net-(D6-PadA)") (class "Default")
      (node (ref "D6") (pin "A") (pinfunction "A_A") (pintype "passive"))
      (node (ref "R40") (pin "1") (pinfunction "1_1") (pintype "passive"))
    )
    (net (code "37") (name "Net-(D8-PadA)") (class "Default")
      (node (ref "D8") (pin "A") (pinfunction "A_A") (pintype "passive"))
      (node (ref "R42") (pin "1") (pinfunction "1_1") (pintype "passive"))
    )
    (net (code "38") (name "Net-(D9-PadA)") (class "Default")
      (node (ref "D9") (pin "A") (pinfunction "A_A") (pintype "passive"))
      (node (ref "R45") (pin "1") (pinfunction "1_1") (pintype "passive"))
    )
    (net (code "39") (name "Net-(D10-PadA)") (class "Default")
      (node (ref "D10") (pin "A") (pinfunction "A_A") (pintype "passive"))
      (node (ref "R48") (pin "1") (pinfunction "1_1") (pintype "passive"))
    )
    (net (code "40") (name "Net-(U1-CFG_SEL2)") (class "Default")
      (node (ref "R57") (pin "2") (pinfunction "2_2") (pintype "passive"))
      (node (ref "U1") (pin "13") (pinfunction "CFG_SEL2_13") (pintype "input"))
    )
    (net (code "41") (name "Net-(U1-HS_IND{slash}CFG_SEL1)") (class "Default")
      (node (ref "R51") (pin "2") (pinfunction "2_2") (pintype "passive"))
      (node (ref "U1") (pin "42") (pinfunction "HS_IND/CFG_SEL1_42") (pintype "bidirectional"))
    )
    (net (code "42") (name "Net-(U1-RBIAS)") (class "Default")
      (node (ref "R35") (pin "1") (pinfunction "1_1") (pintype "passive"))
      (node (ref "U1") (pin "63") (pinfunction "RBIAS_63") (pintype "input"))
    )
    (net (code "43") (name "Net-(U1-SCL{slash}SMBCLK{slash}CFG_SEL0)") (class "Default")
      (node (ref "R50") (pin "2") (pinfunction "2_2") (pintype "passive"))
      (node (ref "U1") (pin "41") (pinfunction "SCL/SMBCLK/CFG_SEL0_41") (pintype "bidirectional"))
    )
    (net (code "44") (name "Net-(U1-SUSP_IND{slash}LOCAL_PWR{slash}NON_REM0)") (class "Default")
      (node (ref "R19") (pin "1") (pinfunction "1_1") (pintype "passive"))
      (node (ref "U1") (pin "45") (pinfunction "SUSP_IND/LOCAL_PWR/NON_REM0_45") (pintype "bidirectional"))
    )
    (net (code "45") (name "Net-(U1-USBDN1_DM{slash}PRT_DIS_M1)") (class "Default")
      (node (ref "R14") (pin "1") (pinfunction "1_1") (pintype "passive"))
      (node (ref "U1") (pin "1") (pinfunction "USBDN1_DM/PRT_DIS_M1_1") (pintype "bidirectional"))
    )
    (net (code "46") (name "Net-(U1-USBDN1_DP{slash}PRT_DIS_P1)") (class "Default")
      (node (ref "R2") (pin "1") (pinfunction "1_1") (pintype "passive"))
      (node (ref "U1") (pin "2") (pinfunction "USBDN1_DP/PRT_DIS_P1_2") (pintype "bidirectional"))
    )
    (net (code "47") (name "Net-(U1-USBDN2_DM{slash}PRT_DIS_M2)") (class "Default")
      (node (ref "R15") (pin "1") (pinfunction "1_1") (pintype "passive"))
      (node (ref "U1") (pin "3") (pinfunction "USBDN2_DM/PRT_DIS_M2_3") (pintype "bidirectional"))
    )
    (net (code "48") (name "Net-(U1-USBDN2_DP{slash}PRT_DIS_P2)") (class "Default")
      (node (ref "R6") (pin "1") (pinfunction "1_1") (pintype "passive"))
      (node (ref "U1") (pin "4") (pinfunction "USBDN2_DP/PRT_DIS_P2_4") (pintype "bidirectional"))
    )
    (net (code "49") (name "Net-(U1-USBDN3_DM{slash}PRT_DIS_M3)") (class "Default")
      (node (ref "R16") (pin "1") (pinfunction "1_1") (pintype "passive"))
      (node (ref "U1") (pin "6") (pinfunction "USBDN3_DM/PRT_DIS_M3_6") (pintype "bidirectional"))
    )
    (net (code "50") (name "Net-(U1-USBDN3_DP{slash}PRT_DIS_P3)") (class "Default")
      (node (ref "R8") (pin "1") (pinfunction "1_1") (pintype "passive"))
      (node (ref "U1") (pin "7") (pinfunction "USBDN3_DP/PRT_DIS_P3_7") (pintype "bidirectional"))
    )
    (net (code "51") (name "Net-(U1-USBDN4_DM{slash}PRT_DIS_M4)") (class "Default")
      (node (ref "R17") (pin "1") (pinfunction "1_1") (pintype "passive"))
      (node (ref "U1") (pin "8") (pinfunction "USBDN4_DM/PRT_DIS_M4_8") (pintype "bidirectional"))
    )
    (net (code "52") (name "Net-(U1-USBDN4_DP{slash}PRT_DIS_P4)") (class "Default")
      (node (ref "R9") (pin "1") (pinfunction "1_1") (pintype "passive"))
      (node (ref "U1") (pin "9") (pinfunction "USBDN4_DP/PRT_DIS_P4_9") (pintype "bidirectional"))
    )
    (net (code "53") (name "Net-(U1-USBDN5_DM{slash}PRT_DIS_M5)") (class "Default")
      (node (ref "R18") (pin "1") (pinfunction "1_1") (pintype "passive"))
      (node (ref "U1") (pin "11") (pinfunction "USBDN5_DM/PRT_DIS_M5_11") (pintype "bidirectional"))
    )
    (net (code "54") (name "Net-(U1-USBDN5_DP{slash}PRT_DIS_P5)") (class "Default")
      (node (ref "R10") (pin "1") (pinfunction "1_1") (pintype "passive"))
      (node (ref "U1") (pin "12") (pinfunction "USBDN5_DP/PRT_DIS_P5_12") (pintype "bidirectional"))
    )
    (net (code "55") (name "Net-(U1-USBDN6_DM{slash}PRT_DIS_M6)") (class "Default")
      (node (ref "R26") (pin "1") (pinfunction "1_1") (pintype "passive"))
      (node (ref "U1") (pin "53") (pinfunction "USBDN6_DM/PRT_DIS_M6_53") (pintype "bidirectional"))
    )
    (net (code "56") (name "Net-(U1-USBDN6_DP{slash}PRT_DIS_P6)") (class "Default")
      (node (ref "R11") (pin "1") (pinfunction "1_1") (pintype "passive"))
      (node (ref "U1") (pin "54") (pinfunction "USBDN6_DP/PRT_DIS_P6_54") (pintype "bidirectional"))
    )
    (net (code "57") (name "Net-(U1-USBDN7_DM{slash}PRT_DIS_M7)") (class "Default")
      (node (ref "R28") (pin "1") (pinfunction "1_1") (pintype "passive"))
      (node (ref "U1") (pin "55") (pinfunction "USBDN7_DM/PRT_DIS_M7_55") (pintype "bidirectional"))
    )
    (net (code "58") (name "Net-(U1-USBDN7_DP{slash}PRT_DIS_P7)") (class "Default")
      (node (ref "R12") (pin "1") (pinfunction "1_1") (pintype "passive"))
      (node (ref "U1") (pin "56") (pinfunction "USBDN7_DP/PRT_DIS_P7_56") (pintype "bidirectional"))
    )
    (net (code "59") (name "Net-(U1-USBUP_DM)") (class "Default")
      (node (ref "R7") (pin "2") (pinfunction "2_2") (pintype "passive"))
      (node (ref "U1") (pin "58") (pinfunction "USBUP_DM_58") (pintype "bidirectional"))
    )
    (net (code "60") (name "Net-(U1-USBUP_DP)") (class "Default")
      (node (ref "R1") (pin "2") (pinfunction "2_2") (pintype "passive"))
      (node (ref "U1") (pin "59") (pinfunction "USBUP_DP_59") (pintype "bidirectional"))
    )
    (net (code "61") (name "Net-(U1-XTAL1{slash}CLKIN)") (class "Default")
      (node (ref "C4") (pin "2") (pinfunction "2_2") (pintype "passive"))
      (node (ref "R30") (pin "2") (pinfunction "2_2") (pintype "passive"))
      (node (ref "U1") (pin "61") (pinfunction "XTAL1/CLKIN_61") (pintype "input"))
      (node (ref "Y1") (pin "3") (pinfunction "OSC2_3") (pintype "passive"))
    )
    (net (code "62") (name "Net-(U1-XTAL2)") (class "Default")
      (node (ref "C5") (pin "2") (pinfunction "2_2") (pintype "passive"))
      (node (ref "R30") (pin "1") (pinfunction "1_1") (pintype "passive"))
      (node (ref "U1") (pin "60") (pinfunction "XTAL2_60") (pintype "passive"))
      (node (ref "Y1") (pin "1") (pinfunction "OSC1_1") (pintype "passive"))
    )
    (net (code "63") (name "Net-(U3-ILIM)") (class "Default")
      (node (ref "R29") (pin "2") (pinfunction "2_2") (pintype "passive"))
      (node (ref "U3") (pin "5") (pinfunction "ILIM_5") (pintype "passive"))
    )
    (net (code "64") (name "Net-(U7-ILIM)") (class "Default")
      (node (ref "R37") (pin "2") (pinfunction "2_2") (pintype "passive"))
      (node (ref "U7") (pin "5") (pinfunction "ILIM_5") (pintype "passive"))
    )
    (net (code "65") (name "Net-(U8-ILIM)") (class "Default")
      (node (ref "R41") (pin "2") (pinfunction "2_2") (pintype "passive"))
      (node (ref "U8") (pin "5") (pinfunction "ILIM_5") (pintype "passive"))
    )
    (net (code "66") (name "Net-(U9-ILIM)") (class "Default")
      (node (ref "R44") (pin "2") (pinfunction "2_2") (pintype "passive"))
      (node (ref "U9") (pin "5") (pinfunction "ILIM_5") (pintype "passive"))
    )
    (net (code "67") (name "Net-(U10-ILIM)") (class "Default")
      (node (ref "R46") (pin "2") (pinfunction "2_2") (pintype "passive"))
      (node (ref "U10") (pin "5") (pinfunction "ILIM_5") (pintype "passive"))
    )
    (net (code "68") (name "Net-(U11-ILIM)") (class "Default")
      (node (ref "R49") (pin "2") (pinfunction "2_2") (pintype "passive"))
      (node (ref "U11") (pin "5") (pinfunction "ILIM_5") (pintype "passive"))
    )
    (net (code "69") (name "USB+5V") (class "Default")
      (node (ref "C18") (pin "2") (pinfunction "2_2") (pintype "passive"))
      (node (ref "P1") (pin "1") (pinfunction "VCC_1") (pintype "passive"))
      (node (ref "R4") (pin "2") (pinfunction "2_2") (pintype "passive"))
    )
    (net (code "70") (name "VCC3V3") (class "Default")
      (node (ref "C10") (pin "1") (pinfunction "1_1") (pintype "passive"))
      (node (ref "C11") (pin "2") (pinfunction "2_2") (pintype "passive"))
      (node (ref "C12") (pin "2") (pinfunction "2_2") (pintype "passive"))
      (node (ref "C13") (pin "2") (pinfunction "2_2") (pintype "passive"))
      (node (ref "C14") (pin "2") (pinfunction "2_2") (pintype "passive"))
      (node (ref "C15") (pin "2") (pinfunction "2_2") (pintype "passive"))
      (node (ref "C22") (pin "2") (pinfunction "2_2") (pintype "passive"))
      (node (ref "R13") (pin "2") (pinfunction "2_2") (pintype "passive"))
      (node (ref "R19") (pin "2") (pinfunction "2_2") (pintype "passive"))
      (node (ref "R31") (pin "2") (pinfunction "2_2") (pintype "passive"))
      (node (ref "R38") (pin "2") (pinfunction "2_2") (pintype "passive"))
      (node (ref "R39") (pin "2") (pinfunction "2_2") (pintype "passive"))
      (node (ref "R43") (pin "2") (pinfunction "2_2") (pintype "passive"))
      (node (ref "R47") (pin "2") (pinfunction "2_2") (pintype "passive"))
      (node (ref "R50") (pin "1") (pinfunction "1_1") (pintype "passive"))
      (node (ref "R57") (pin "1") (pinfunction "1_1") (pintype "passive"))
      (node (ref "U1") (pin "10") (pinfunction "VDDA33_10") (pintype "power_in"))
      (node (ref "U1") (pin "24") (pinfunction "VDD33CR_24") (pintype "power_in"))
      (node (ref "U1") (pin "46") (pinfunction "VDD33_46") (pintype "power_in"))
      (node (ref "U1") (pin "5") (pinfunction "VDDA33_5") (pintype "power_in"))
      (node (ref "U1") (pin "52") (pinfunction "VDDA33_52") (pintype "power_in"))
      (node (ref "U1") (pin "57") (pinfunction "VDDA33_57") (pintype "power_in"))
      (node (ref "U1") (pin "64") (pinfunction "VDD33PLL_64") (pintype "power_in"))
    )
    (net (code "71") (name "VCC5V") (class "Default")
      (node (ref "C1") (pin "1") (pinfunction "1_1") (pintype "passive"))
      (node (ref "C23") (pin "1") (pinfunction "1_1") (pintype "passive"))
      (node (ref "C24") (pin "1") (pinfunction "1_1") (pintype "passive"))
      (node (ref "C32") (pin "1") (pinfunction "1_1") (pintype "passive"))
      (node (ref "C34") (pin "1") (pinfunction "1_1") (pintype "passive"))
      (node (ref "C6") (pin "1") (pinfunction "1_1") (pintype "passive"))
      (node (ref "U10") (pin "1") (pinfunction "IN_1") (pintype "passive"))
      (node (ref "U11") (pin "1") (pinfunction "IN_1") (pintype "passive"))
      (node (ref "U3") (pin "1") (pinfunction "IN_1") (pintype "passive"))
      (node (ref "U7") (pin "1") (pinfunction "IN_1") (pintype "passive"))
      (node (ref "U8") (pin "1") (pinfunction "IN_1") (pintype "passive"))
      (node (ref "U9") (pin "1") (pinfunction "IN_1") (pintype "passive"))
    )
    (net (code "72") (name "unconnected-(P1-Pad0)") (class "Default")
      (node (ref "P1") (pin "0") (pinfunction "0_0") (pintype "passive"))
    )
    (net (code "73") (name "unconnected-(P2-Pad0)") (class "Default")
      (node (ref "P2") (pin "0") (pinfunction "0_0") (pintype "passive"))
    )
    (net (code "74") (name "unconnected-(P3-Pad0)") (class "Default")
      (node (ref "P3") (pin "0") (pinfunction "0_0") (pintype "passive"))
    )
    (net (code "75") (name "unconnected-(P4-Pad0)") (class "Default")
      (node (ref "P4") (pin "0") (pinfunction "0_0") (pintype "passive"))
    )
    (net (code "76") (name "unconnected-(P5-Pad0)") (class "Default")
      (node (ref "P5") (pin "0") (pinfunction "0_0") (pintype "passive"))
    )
    (net (code "77") (name "unconnected-(P6-Pad0)") (class "Default")
      (node (ref "P6") (pin "0") (pinfunction "0_0") (pintype "passive"))
    )
    (net (code "78") (name "unconnected-(P7-Pad0)") (class "Default")
      (node (ref "P7") (pin "0") (pinfunction "0_0") (pintype "passive"))
    )
    (net (code "79") (name "unconnected-(U1-LED_A1_N{slash}PRT_SWP1-Pad51)") (class "Default")
      (node (ref "U1") (pin "51") (pinfunction "LED_A1_N/PRT_SWP1_51") (pintype "bidirectional+no_connect"))
    )
    (net (code "80") (name "unconnected-(U1-LED_A2_N{slash}PRT_SWP2-Pad49)") (class "Default")
      (node (ref "U1") (pin "49") (pinfunction "LED_A2_N/PRT_SWP2_49") (pintype "bidirectional+no_connect"))
    )
    (net (code "81") (name "unconnected-(U1-LED_A3_N{slash}PRT_SWP3-Pad47)") (class "Default")
      (node (ref "U1") (pin "47") (pinfunction "LED_A3_N/PRT_SWP3_47") (pintype "bidirectional+no_connect"))
    )
    (net (code "82") (name "unconnected-(U1-LED_A4_N{slash}PRT_SWP4-Pad33)") (class "Default")
      (node (ref "U1") (pin "33") (pinfunction "LED_A4_N/PRT_SWP4_33") (pintype "bidirectional+no_connect"))
    )
    (net (code "83") (name "unconnected-(U1-LED_A5_N{slash}PRT_SWP5-Pad31)") (class "Default")
      (node (ref "U1") (pin "31") (pinfunction "LED_A5_N/PRT_SWP5_31") (pintype "bidirectional+no_connect"))
    )
    (net (code "84") (name "unconnected-(U1-LED_A6_N{slash}PRT_SWP6-Pad17)") (class "Default")
      (node (ref "U1") (pin "17") (pinfunction "LED_A6_N/PRT_SWP6_17") (pintype "bidirectional+no_connect"))
    )
    (net (code "85") (name "unconnected-(U1-LED_A7_N{slash}PRT_SWP7-Pad15)") (class "Default")
      (node (ref "U1") (pin "15") (pinfunction "LED_A7_N/PRT_SWP7_15") (pintype "bidirectional+no_connect"))
    )
    (net (code "86") (name "unconnected-(U1-LED_B1_N{slash}BOOST0-Pad50)") (class "Default")
      (node (ref "U1") (pin "50") (pinfunction "LED_B1_N/BOOST0_50") (pintype "bidirectional+no_connect"))
    )
    (net (code "87") (name "unconnected-(U1-LED_B2_N{slash}BOOST1-Pad48)") (class "Default")
      (node (ref "U1") (pin "48") (pinfunction "LED_B2_N/BOOST1_48") (pintype "bidirectional+no_connect"))
    )
    (net (code "88") (name "unconnected-(U1-LED_B3_N{slash}GANG_EN-Pad34)") (class "Default")
      (node (ref "U1") (pin "34") (pinfunction "LED_B3_N/GANG_EN_34") (pintype "bidirectional+no_connect"))
    )
    (net (code "89") (name "unconnected-(U1-LED_B4_N-Pad32)") (class "Default")
      (node (ref "U1") (pin "32") (pinfunction "LED_B4_N_32") (pintype "bidirectional+no_connect"))
    )
    (net (code "90") (name "unconnected-(U1-LED_B5_N-Pad18)") (class "Default")
      (node (ref "U1") (pin "18") (pinfunction "LED_B5_N_18") (pintype "bidirectional+no_connect"))
    )
    (net (code "91") (name "unconnected-(U1-LED_B6_N-Pad16)") (class "Default")
      (node (ref "U1") (pin "16") (pinfunction "LED_B6_N_16") (pintype "bidirectional+no_connect"))
    )
    (net (code "92") (name "unconnected-(U1-LED_B7_N-Pad14)") (class "Default")
      (node (ref "U1") (pin "14") (pinfunction "LED_B7_N_14") (pintype "bidirectional+no_connect"))
    )
    (net (code "93") (name "unconnected-(U1-OCS1_N-Pad28)") (class "Default")
      (node (ref "U1") (pin "28") (pinfunction "OCS1_N_28") (pintype "input+no_connect"))
    )
    (net (code "94") (name "unconnected-(U1-OCS2_N-Pad27)") (class "Default")
      (node (ref "U1") (pin "27") (pinfunction "OCS2_N_27") (pintype "input+no_connect"))
    )
    (net (code "95") (name "unconnected-(U1-OCS3_N-Pad22)") (class "Default")
      (node (ref "U1") (pin "22") (pinfunction "OCS3_N_22") (pintype "input+no_connect"))
    )
    (net (code "96") (name "unconnected-(U1-OCS4_N-Pad21)") (class "Default")
      (node (ref "U1") (pin "21") (pinfunction "OCS4_N_21") (pintype "input+no_connect"))
    )
    (net (code "97") (name "unconnected-(U1-OCS5_N-Pad35)") (class "Default")
      (node (ref "U1") (pin "35") (pinfunction "OCS5_N_35") (pintype "input+no_connect"))
    )
    (net (code "98") (name "unconnected-(U1-OCS6_N-Pad38)") (class "Default")
      (node (ref "U1") (pin "38") (pinfunction "OCS6_N_38") (pintype "input+no_connect"))
    )
    (net (code "99") (name "unconnected-(U1-OCS7_N-Pad37)") (class "Default")
      (node (ref "U1") (pin "37") (pinfunction "OCS7_N_37") (pintype "input+no_connect"))
    )
    (net (code "100") (name "unconnected-(U1-PRTPWR1-Pad29)") (class "Default")
      (node (ref "U1") (pin "29") (pinfunction "PRTPWR1_29") (pintype "output+no_connect"))
    )
    (net (code "101") (name "unconnected-(U1-PRTPWR2-Pad26)") (class "Default")
      (node (ref "U1") (pin "26") (pinfunction "PRTPWR2_26") (pintype "output+no_connect"))
    )
    (net (code "102") (name "unconnected-(U1-PRTPWR3-Pad23)") (class "Default")
      (node (ref "U1") (pin "23") (pinfunction "PRTPWR3_23") (pintype "output+no_connect"))
    )
    (net (code "103") (name "unconnected-(U1-PRTPWR4-Pad20)") (class "Default")
      (node (ref "U1") (pin "20") (pinfunction "PRTPWR4_20") (pintype "output+no_connect"))
    )
    (net (code "104") (name "unconnected-(U1-PRTPWR5-Pad30)") (class "Default")
      (node (ref "U1") (pin "30") (pinfunction "PRTPWR5_30") (pintype "output+no_connect"))
    )
    (net (code "105") (name "unconnected-(U1-PRTPWR6-Pad39)") (class "Default")
      (node (ref "U1") (pin "39") (pinfunction "PRTPWR6_39") (pintype "output+no_connect"))
    )
    (net (code "106") (name "unconnected-(U1-PRTPWR7-Pad36)") (class "Default")
      (node (ref "U1") (pin "36") (pinfunction "PRTPWR7_36") (pintype "output+no_connect"))
    )
    (net (code "107") (name "unconnected-(U1-SDA{slash}SMBDATA{slash}NON_REM1-Pad40)") (class "Default")
      (node (ref "U1") (pin "40") (pinfunction "SDA/SMBDATA/NON_REM1_40") (pintype "bidirectional"))
    )
    (net (code "108") (name "unconnected-(U3-~{FAULT}-Pad4)") (class "Default")
      (node (ref "U3") (pin "4") (pinfunction "~{FAULT}_4") (pintype "passive+no_connect"))
    )
    (net (code "109") (name "unconnected-(U7-~{FAULT}-Pad4)") (class "Default")
      (node (ref "U7") (pin "4") (pinfunction "~{FAULT}_4") (pintype "passive+no_connect"))
    )
    (net (code "110") (name "unconnected-(U8-~{FAULT}-Pad4)") (class "Default")
      (node (ref "U8") (pin "4") (pinfunction "~{FAULT}_4") (pintype "passive+no_connect"))
    )
    (net (code "111") (name "unconnected-(U9-~{FAULT}-Pad4)") (class "Default")
      (node (ref "U9") (pin "4") (pinfunction "~{FAULT}_4") (pintype "passive+no_connect"))
    )
    (net (code "112") (name "unconnected-(U10-~{FAULT}-Pad4)") (class "Default")
      (node (ref "U10") (pin "4") (pinfunction "~{FAULT}_4") (pintype "passive+no_connect"))
    )
    (net (code "113") (name "unconnected-(U11-~{FAULT}-Pad4)") (class "Default")
      (node (ref "U11") (pin "4") (pinfunction "~{FAULT}_4") (pintype "passive+no_connect"))
    )
  )
)
